# InrushLimiter.net
KiCad netlist of a schematic drawn in Altium Designer
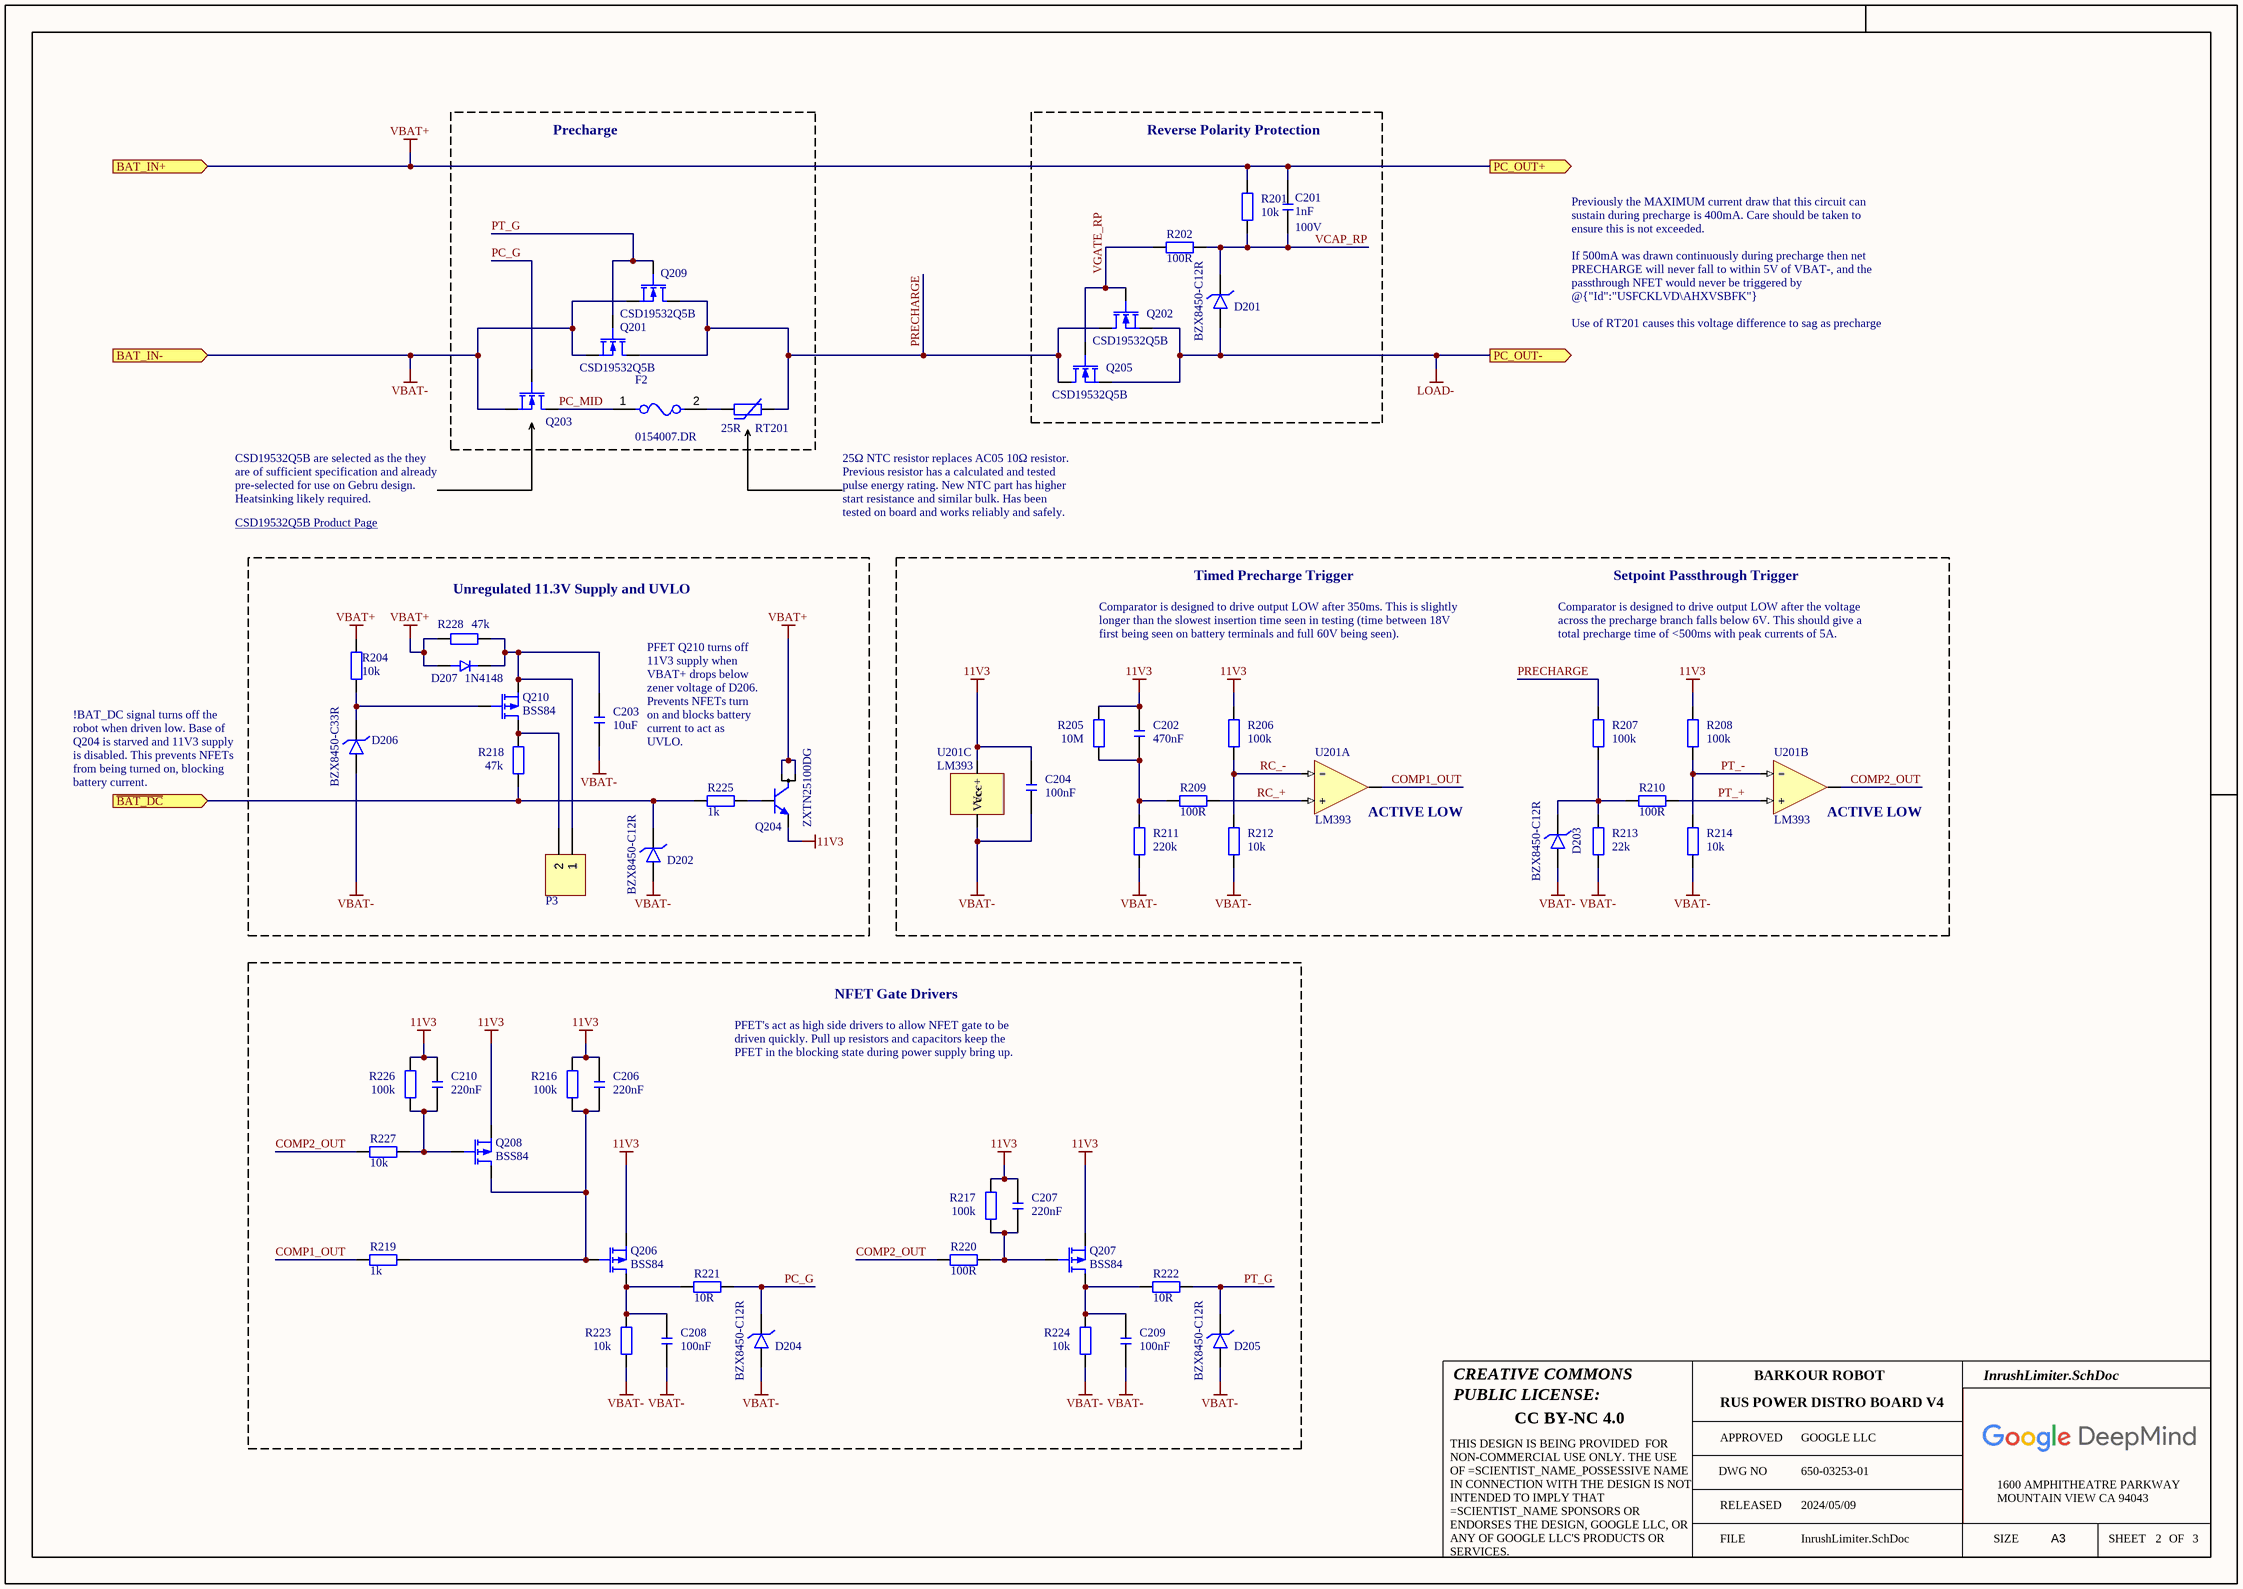
[diagram p0: InrushLimiter.SchDoc]

(export (version "E")
  (design (tool "Eeschema 10.0.6"))
  (components
    (comp (ref "C201")
      (value "1nF")
      (footprint "CAP 0805_2012")
      (description "Generic Capacitor")
      (fields (field (name "TOLERANCE") "20%") (field (name "VOLTAGE RATING") "100V"))
      (libsource (lib "DMR_common_lib") (part "C"))
    )
    (comp (ref "C202")
      (value "470nF")
      (footprint "CAP 0603_1608 RF")
      (description "Generic Capacitor")
      (fields (field (name "TOLERANCE") "10%"))
      (libsource (lib "DMR_common_lib") (part "C"))
    )
    (comp (ref "C203")
      (value "10uF")
      (footprint "CAP 1206_3216")
      (description "Generic Capacitor")
      (fields (field (name "TOLERANCE") "10%"))
      (libsource (lib "DMR_common_lib") (part "C"))
    )
    (comp (ref "C204")
      (value "100nF")
      (footprint "CAP 0603_1608 RF")
      (description "Generic Capacitor")
      (fields (field (name "TOLERANCE") "10%"))
      (libsource (lib "DMR_common_lib") (part "C"))
    )
    (comp (ref "C206")
      (value "220nF")
      (footprint "CAP 0603_1608 RF")
      (description "Generic Capacitor")
      (fields (field (name "TOLERANCE") "10%"))
      (libsource (lib "DMR_common_lib") (part "C"))
    )
    (comp (ref "C207")
      (value "220nF")
      (footprint "CAP 0603_1608 RF")
      (description "Generic Capacitor")
      (fields (field (name "TOLERANCE") "10%"))
      (libsource (lib "DMR_common_lib") (part "C"))
    )
    (comp (ref "C208")
      (value "100nF")
      (footprint "CAP 0603_1608 RF")
      (description "Generic Capacitor")
      (fields (field (name "TOLERANCE") "10%"))
      (libsource (lib "DMR_common_lib") (part "C"))
    )
    (comp (ref "C209")
      (value "100nF")
      (footprint "CAP 0603_1608 RF")
      (description "Generic Capacitor")
      (fields (field (name "TOLERANCE") "10%"))
      (libsource (lib "DMR_common_lib") (part "C"))
    )
    (comp (ref "C210")
      (value "220nF")
      (footprint "CAP 0603_1608 RF")
      (description "Generic Capacitor")
      (fields (field (name "TOLERANCE") "10%"))
      (libsource (lib "DMR_common_lib") (part "C"))
    )
    (comp (ref "D201")
      (value "BZX8450-C12R")
      (footprint "NEXPERIA SOT-23-3")
      (description "Diode Zener Single 12V 5% 250mW 3-Pin SOT-23 T/R")
      (fields (field (name "MANUFACTURER") "Nexperia"))
      (libsource (lib "DMR_common_lib") (part "BZX8450-C12R"))
    )
    (comp (ref "D202")
      (value "BZX8450-C12R")
      (footprint "NEXPERIA SOT-23-3")
      (description "Diode Zener Single 12V 5% 250mW 3-Pin SOT-23 T/R")
      (fields (field (name "MANUFACTURER") "Nexperia"))
      (libsource (lib "DMR_common_lib") (part "BZX8450-C12R"))
    )
    (comp (ref "D203")
      (value "BZX8450-C12R")
      (footprint "NEXPERIA SOT-23-3")
      (description "Diode Zener Single 12V 5% 250mW 3-Pin SOT-23 T/R")
      (fields (field (name "MANUFACTURER") "Nexperia"))
      (libsource (lib "DMR_common_lib") (part "BZX8450-C12R"))
    )
    (comp (ref "D204")
      (value "BZX8450-C12R")
      (footprint "NEXPERIA SOT-23-3")
      (description "Diode Zener Single 12V 5% 250mW 3-Pin SOT-23 T/R")
      (fields (field (name "MANUFACTURER") "Nexperia"))
      (libsource (lib "DMR_common_lib") (part "BZX8450-C12R"))
    )
    (comp (ref "D205")
      (value "BZX8450-C12R")
      (footprint "NEXPERIA SOT-23-3")
      (description "Diode Zener Single 12V 5% 250mW 3-Pin SOT-23 T/R")
      (fields (field (name "MANUFACTURER") "Nexperia"))
      (libsource (lib "DMR_common_lib") (part "BZX8450-C12R"))
    )
    (comp (ref "D206")
      (value "BZX8450-C33R")
      (footprint "NEXPERIA SOT-23-3")
      (description "Zener Diodes BZX8450-C33/SOT23/TO-236AB")
      (fields (field (name "MANUFACTURER") "Nexperia"))
      (libsource (lib "DMR_common_lib") (part "BZX8450-C20R"))
    )
    (comp (ref "D207")
      (value "1N4148WS-7-F")
      (footprint "SOD323")
      (description "Signal Diode VR=75V IF=150mA Trr=4ns P=200mW")
      (fields
        (field (name "MANUFACTURER") "Diodes")
        (field (name "VOLTAGE") "75V")
        (field (name "COLLOQUIAL") "1N4148")
      )
      (libsource (lib "DMR_common_lib") (part "1N4148"))
    )
    (comp (ref "F2")
      (value "0154007.DR")
      (footprint "FP-0154-MFG")
      (description "FUSE BRD MNT 7A 125VAC/VDC 2SMD")
      (fields
        (field (name "OCTOPART") "https://octopart.com/0154007.dr-littelfuse-565863")
        (field (name "MANUFACTURER") "Littelfuse Inc")
      )
      (libsource (lib "Altium Content Vault") (part "5bcf9b9f640e542cf0359d10258e979"))
    )
    (comp (ref "P3")
      (value "Header 2")
      (footprint "HDR1X2")
      (description "Header, 2-Pin")
      (fields (field (name "PUBLISHER") "Altium Limited"))
      (libsource (lib "Miscellaneous Connectors") (part "Header 2"))
    )
    (comp (ref "Q201")
      (value "CSD19532Q5B")
      (footprint "TI SON 5x6")
      (description "100-V, N channel NexFET™ power MOSFET, single SON 5 mm x 6 mm, 4.9 mOhm 8-VSON-CLIP -55 to 150")
      (fields (field (name "MANUFACTURER") "Texas Instruments"))
      (libsource (lib "DMR_common_lib") (part "CSD19532Q5B"))
    )
    (comp (ref "Q202")
      (value "CSD19532Q5B")
      (footprint "TI SON 5x6")
      (description "100-V, N channel NexFET™ power MOSFET, single SON 5 mm x 6 mm, 4.9 mOhm 8-VSON-CLIP -55 to 150")
      (fields (field (name "MANUFACTURER") "Texas Instruments"))
      (libsource (lib "DMR_common_lib") (part "CSD19532Q5B"))
    )
    (comp (ref "Q203")
      (value "CSD19532Q5B")
      (footprint "TI SON 5x6")
      (description "100-V, N channel NexFET™ power MOSFET, single SON 5 mm x 6 mm, 4.9 mOhm 8-VSON-CLIP -55 to 150")
      (fields (field (name "MANUFACTURER") "Texas Instruments"))
      (libsource (lib "DMR_common_lib") (part "CSD19532Q5B"))
    )
    (comp (ref "Q204")
      (value "ZXTN25100DG")
      (footprint "DIODES SOT-223")
      (description "TRANS NPN 100V 3A SOT223")
      (fields (field (name "MANUFACTURER") "Diodes Inc"))
      (libsource (lib "DMR_common_lib") (part "ZXTN25100DG"))
    )
    (comp (ref "Q205")
      (value "CSD19532Q5B")
      (footprint "TI SON 5x6")
      (description "100-V, N channel NexFET™ power MOSFET, single SON 5 mm x 6 mm, 4.9 mOhm 8-VSON-CLIP -55 to 150")
      (fields (field (name "MANUFACTURER") "Texas Instruments"))
      (libsource (lib "DMR_common_lib") (part "CSD19532Q5B"))
    )
    (comp (ref "Q206")
      (value "BSS84W-7-F")
      (footprint "DIODES SOT-323-3")
      (description "P-Channel 50 V 10 Ohm Enhancement Mode Transistor SOT-323")
      (fields (field (name "MANUFACTURER") "Diodes Inc") (field (name "COLLOQUIAL") "BSS84"))
      (libsource (lib "DMR_common_lib") (part "BSS84W"))
    )
    (comp (ref "Q207")
      (value "BSS84W-7-F")
      (footprint "DIODES SOT-323-3")
      (description "P-Channel 50 V 10 Ohm Enhancement Mode Transistor SOT-323")
      (fields (field (name "MANUFACTURER") "Diodes Inc") (field (name "COLLOQUIAL") "BSS84"))
      (libsource (lib "DMR_common_lib") (part "BSS84W"))
    )
    (comp (ref "Q208")
      (value "BSS84W-7-F")
      (footprint "DIODES SOT-323-3")
      (description "P-Channel 50 V 10 Ohm Enhancement Mode Transistor SOT-323")
      (fields (field (name "MANUFACTURER") "Diodes Inc") (field (name "COLLOQUIAL") "BSS84"))
      (libsource (lib "DMR_common_lib") (part "BSS84W"))
    )
    (comp (ref "Q209")
      (value "CSD19532Q5B")
      (footprint "TI SON 5x6")
      (description "100-V, N channel NexFET™ power MOSFET, single SON 5 mm x 6 mm, 4.9 mOhm 8-VSON-CLIP -55 to 150")
      (fields (field (name "MANUFACTURER") "Texas Instruments"))
      (libsource (lib "DMR_common_lib") (part "CSD19532Q5B"))
    )
    (comp (ref "Q210")
      (value "BSS84W-7-F")
      (footprint "DIODES SOT-323-3")
      (description "P-Channel 50 V 10 Ohm Enhancement Mode Transistor SOT-323")
      (fields (field (name "MANUFACTURER") "Diodes Inc") (field (name "COLLOQUIAL") "BSS84"))
      (libsource (lib "DMR_common_lib") (part "BSS84W"))
    )
    (comp (ref "R201")
      (value "10k")
      (footprint "RES 0402_1005 RF")
      (description "Generic Resistor")
      (fields (field (name "TOLERANCE") "1%"))
      (libsource (lib "DMR_common_lib") (part "R"))
    )
    (comp (ref "R202")
      (value "100R")
      (footprint "RES 0402_1005 RF")
      (description "Generic Resistor")
      (fields (field (name "TOLERANCE") "1%"))
      (libsource (lib "") (part "R_2"))
    )
    (comp (ref "R204")
      (value "10k")
      (footprint "RES 0603_1608 RF")
      (description "RES 10K OHM 1% 1/5W 0603")
      (fields (field (name "TOLERANCE") "1%") (field (name "MANUFACTURER") "YAGEO"))
      (libsource (lib "") (part "R_1"))
    )
    (comp (ref "R205")
      (value "10M")
      (footprint "RES 0402_1005 RF")
      (description "Generic Resistor")
      (fields (field (name "TOLERANCE") "1%"))
      (libsource (lib "DMR_common_lib") (part "R"))
    )
    (comp (ref "R206")
      (value "100k")
      (footprint "RES 0402_1005 RF")
      (description "Generic Resistor")
      (fields (field (name "TOLERANCE") "1%"))
      (libsource (lib "DMR_common_lib") (part "R"))
    )
    (comp (ref "R207")
      (value "100k")
      (footprint "RES 0402_1005 RF")
      (description "Generic Resistor")
      (fields (field (name "TOLERANCE") "1%"))
      (libsource (lib "DMR_common_lib") (part "R"))
    )
    (comp (ref "R208")
      (value "100k")
      (footprint "RES 0402_1005 RF")
      (description "Generic Resistor")
      (fields (field (name "TOLERANCE") "1%"))
      (libsource (lib "DMR_common_lib") (part "R"))
    )
    (comp (ref "R209")
      (value "100R")
      (footprint "RES 0402_1005 RF")
      (description "Generic Resistor")
      (fields (field (name "TOLERANCE") "1%"))
      (libsource (lib "") (part "R_2"))
    )
    (comp (ref "R210")
      (value "100R")
      (footprint "RES 0402_1005 RF")
      (description "Generic Resistor")
      (fields (field (name "TOLERANCE") "1%"))
      (libsource (lib "") (part "R_2"))
    )
    (comp (ref "R211")
      (value "220k")
      (footprint "RES 0402_1005 RF")
      (description "Generic Resistor")
      (fields (field (name "TOLERANCE") "1%"))
      (libsource (lib "DMR_common_lib") (part "R"))
    )
    (comp (ref "R212")
      (value "10k")
      (footprint "RES 0402_1005 RF")
      (description "Generic Resistor")
      (fields (field (name "TOLERANCE") "1%"))
      (libsource (lib "DMR_common_lib") (part "R"))
    )
    (comp (ref "R213")
      (value "22k")
      (footprint "RES 0603_1608 RF")
      (description "Generic Resistor")
      (fields (field (name "TOLERANCE") "1%"))
      (libsource (lib "DMR_common_lib") (part "R"))
    )
    (comp (ref "R214")
      (value "10k")
      (footprint "RES 0402_1005 RF")
      (description "Generic Resistor")
      (fields (field (name "TOLERANCE") "1%"))
      (libsource (lib "DMR_common_lib") (part "R"))
    )
    (comp (ref "R216")
      (value "100k")
      (footprint "RES 0402_1005 RF")
      (description "Generic Resistor")
      (fields (field (name "TOLERANCE") "1%"))
      (libsource (lib "") (part "R_1"))
    )
    (comp (ref "R217")
      (value "100k")
      (footprint "RES 0402_1005 RF")
      (description "Generic Resistor")
      (fields (field (name "TOLERANCE") "1%"))
      (libsource (lib "") (part "R_1"))
    )
    (comp (ref "R218")
      (value "47k")
      (footprint "RES 0603_1608 RF")
      (description "Generic Resistor")
      (fields (field (name "TOLERANCE") "1%"))
      (libsource (lib "DMR_common_lib") (part "R"))
    )
    (comp (ref "R219")
      (value "1k")
      (footprint "RES 0402_1005 RF")
      (description "Generic Resistor")
      (fields (field (name "TOLERANCE") "1%"))
      (libsource (lib "") (part "R_2"))
    )
    (comp (ref "R220")
      (value "100R")
      (footprint "RES 0402_1005 RF")
      (description "Generic Resistor")
      (fields (field (name "TOLERANCE") "1%"))
      (libsource (lib "") (part "R_2"))
    )
    (comp (ref "R221")
      (value "10R")
      (footprint "RES 0402_1005 RF")
      (description "Generic Resistor")
      (fields (field (name "TOLERANCE") "1%"))
      (libsource (lib "") (part "R_2"))
    )
    (comp (ref "R222")
      (value "10R")
      (footprint "RES 0402_1005 RF")
      (description "Generic Resistor")
      (fields (field (name "TOLERANCE") "1%"))
      (libsource (lib "") (part "R_2"))
    )
    (comp (ref "R223")
      (value "10k")
      (footprint "RES 0402_1005 RF")
      (description "Generic Resistor")
      (fields (field (name "TOLERANCE") "1%"))
      (libsource (lib "") (part "R_1"))
    )
    (comp (ref "R224")
      (value "10k")
      (footprint "RES 0402_1005 RF")
      (description "Generic Resistor")
      (fields (field (name "TOLERANCE") "1%"))
      (libsource (lib "") (part "R_1"))
    )
    (comp (ref "R225")
      (value "1k")
      (footprint "RES 0603_1608 RF")
      (description "Generic Resistor")
      (fields (field (name "TOLERANCE") "1%"))
      (libsource (lib "") (part "R_2"))
    )
    (comp (ref "R226")
      (value "100k")
      (footprint "RES 0402_1005 RF")
      (description "Generic Resistor")
      (fields (field (name "TOLERANCE") "1%"))
      (libsource (lib "") (part "R_1"))
    )
    (comp (ref "R227")
      (value "10k")
      (footprint "RES 0402_1005 RF")
      (description "Generic Resistor")
      (fields (field (name "TOLERANCE") "1%"))
      (libsource (lib "") (part "R_2"))
    )
    (comp (ref "R228")
      (value "47k")
      (footprint "RES 0603_1608 RF")
      (description "Generic Resistor")
      (fields (field (name "TOLERANCE") "1%"))
      (libsource (lib "") (part "R_2"))
    )
    (comp (ref "RT201")
      (value "25R")
      (footprint "RES THERM TH 16.0 DISC LEADED")
      (description "NTC Thermistor, 25ohm, Through Hole Mount")
      (fields
        (field (name "MANUFACTURER") "Epcos")
        (field (name "MANUFACTURER PART NUMBER") "B57238S0250M000")
      )
      (libsource (lib "DMR_common_lib") (part "B57238S0250M000"))
    )
    (comp (ref "U201")
      (value "LM393PT")
      (footprint "ST TSSOP-8")
      (description "Comparator Dual 18V/36V 8-Pin TSSOP T/R")
      (fields (field (name "MANUFACTURER") "ST") (field (name "COLLOQUIAL") "LM393"))
      (libsource (lib "DMR_common_lib") (part "LM393"))
    )
  )
  (nets
    (net (code "1") (name "/COMP1_OUT") (class "Default")
      (node (ref "R219") (pin "2") (pinfunction "2_2") (pintype "passive"))
      (node (ref "U201") (pin "1") (pinfunction "Out1_1") (pintype "open_collector"))
    )
    (net (code "2") (name "/COMP2_OUT") (class "Default")
      (node (ref "R220") (pin "2") (pinfunction "2_2") (pintype "passive"))
      (node (ref "R227") (pin "2") (pinfunction "2_2") (pintype "passive"))
      (node (ref "U201") (pin "7") (pinfunction "Out1_7") (pintype "open_collector"))
    )
    (net (code "3") (name "/PC_G") (class "Default")
      (node (ref "D204") (pin "3") (pinfunction "K_3") (pintype "passive"))
      (node (ref "Q203") (pin "1") (pinfunction "G_1") (pintype "passive"))
      (node (ref "R221") (pin "1") (pinfunction "1_1") (pintype "passive"))
    )
    (net (code "4") (name "/PC_MID") (class "Default")
      (node (ref "F2") (pin "1") (pinfunction "1_1") (pintype "passive"))
      (node (ref "Q203") (pin "3") (pinfunction "D_3") (pintype "passive"))
    )
    (net (code "5") (name "/PRECHARGE") (class "Default")
      (node (ref "Q201") (pin "3") (pinfunction "D_3") (pintype "passive"))
      (node (ref "Q202") (pin "3") (pinfunction "D_3") (pintype "passive"))
      (node (ref "Q205") (pin "3") (pinfunction "D_3") (pintype "passive"))
      (node (ref "Q209") (pin "3") (pinfunction "D_3") (pintype "passive"))
      (node (ref "R207") (pin "2") (pinfunction "2_2") (pintype "passive"))
      (node (ref "RT201") (pin "2") (pinfunction "2_2") (pintype "passive"))
    )
    (net (code "6") (name "/PT_+") (class "Default")
      (node (ref "R210") (pin "1") (pinfunction "1_1") (pintype "passive"))
      (node (ref "U201") (pin "5") (pinfunction "+_5") (pintype "input"))
    )
    (net (code "7") (name "/PT_-") (class "Default")
      (node (ref "R208") (pin "1") (pinfunction "1_1") (pintype "passive"))
      (node (ref "R214") (pin "2") (pinfunction "2_2") (pintype "passive"))
      (node (ref "U201") (pin "6") (pinfunction "−_6") (pintype "input"))
    )
    (net (code "8") (name "/PT_G") (class "Default")
      (node (ref "D205") (pin "3") (pinfunction "K_3") (pintype "passive"))
      (node (ref "Q201") (pin "1") (pinfunction "G_1") (pintype "passive"))
      (node (ref "Q209") (pin "1") (pinfunction "G_1") (pintype "passive"))
      (node (ref "R222") (pin "1") (pinfunction "1_1") (pintype "passive"))
    )
    (net (code "9") (name "/RC_+") (class "Default")
      (node (ref "R209") (pin "1") (pinfunction "1_1") (pintype "passive"))
      (node (ref "U201") (pin "3") (pinfunction "+_3") (pintype "input"))
    )
    (net (code "10") (name "/RC_-") (class "Default")
      (node (ref "R206") (pin "1") (pinfunction "1_1") (pintype "passive"))
      (node (ref "R212") (pin "2") (pinfunction "2_2") (pintype "passive"))
      (node (ref "U201") (pin "2") (pinfunction "−_2") (pintype "input"))
    )
    (net (code "11") (name "/VCAP_RP") (class "Default")
      (node (ref "C201") (pin "1") (pinfunction "1_1") (pintype "passive"))
      (node (ref "D201") (pin "3") (pinfunction "K_3") (pintype "passive"))
      (node (ref "R201") (pin "1") (pinfunction "1_1") (pintype "passive"))
      (node (ref "R202") (pin "1") (pinfunction "1_1") (pintype "passive"))
    )
    (net (code "12") (name "/VGATE_RP") (class "Default")
      (node (ref "Q202") (pin "1") (pinfunction "G_1") (pintype "passive"))
      (node (ref "Q205") (pin "1") (pinfunction "G_1") (pintype "passive"))
      (node (ref "R202") (pin "2") (pinfunction "2_2") (pintype "passive"))
    )
    (net (code "13") (name "/~{BAT_DC}") (class "Default")
      (node (ref "D202") (pin "3") (pinfunction "K_3") (pintype "passive"))
      (node (ref "R218") (pin "1") (pinfunction "1_1") (pintype "passive"))
      (node (ref "R225") (pin "2") (pinfunction "2_2") (pintype "passive"))
    )
    (net (code "14") (name "11V3") (class "Default")
      (node (ref "C202") (pin "2") (pinfunction "2_2") (pintype "passive"))
      (node (ref "C204") (pin "2") (pinfunction "2_2") (pintype "passive"))
      (node (ref "C206") (pin "2") (pinfunction "2_2") (pintype "passive"))
      (node (ref "C207") (pin "2") (pinfunction "2_2") (pintype "passive"))
      (node (ref "C210") (pin "2") (pinfunction "2_2") (pintype "passive"))
      (node (ref "Q204") (pin "3") (pinfunction "E_3") (pintype "passive"))
      (node (ref "Q206") (pin "3") (pinfunction "S_3") (pintype "passive"))
      (node (ref "Q207") (pin "3") (pinfunction "S_3") (pintype "passive"))
      (node (ref "Q208") (pin "3") (pinfunction "S_3") (pintype "passive"))
      (node (ref "R205") (pin "2") (pinfunction "2_2") (pintype "passive"))
      (node (ref "R206") (pin "2") (pinfunction "2_2") (pintype "passive"))
      (node (ref "R208") (pin "2") (pinfunction "2_2") (pintype "passive"))
      (node (ref "R216") (pin "1") (pinfunction "1_1") (pintype "passive"))
      (node (ref "R217") (pin "1") (pinfunction "1_1") (pintype "passive"))
      (node (ref "R226") (pin "1") (pinfunction "1_1") (pintype "passive"))
      (node (ref "U201") (pin "8") (pinfunction "Vcc+_8") (pintype "power_in"))
    )
    (net (code "15") (name "LOAD-") (class "Default")
      (node (ref "D201") (pin "1") (pinfunction "A_1") (pintype "passive"))
      (node (ref "Q202") (pin "2") (pinfunction "S_2") (pintype "passive"))
      (node (ref "Q205") (pin "2") (pinfunction "S_2") (pintype "passive"))
    )
    (net (code "16") (name "Net-(C202-Pad1)") (class "Default")
      (node (ref "C202") (pin "1") (pinfunction "1_1") (pintype "passive"))
      (node (ref "R205") (pin "1") (pinfunction "1_1") (pintype "passive"))
      (node (ref "R209") (pin "2") (pinfunction "2_2") (pintype "passive"))
      (node (ref "R211") (pin "2") (pinfunction "2_2") (pintype "passive"))
    )
    (net (code "17") (name "Net-(D203-K)") (class "Default")
      (node (ref "D203") (pin "3") (pinfunction "K_3") (pintype "passive"))
      (node (ref "R207") (pin "1") (pinfunction "1_1") (pintype "passive"))
      (node (ref "R210") (pin "2") (pinfunction "2_2") (pintype "passive"))
      (node (ref "R213") (pin "2") (pinfunction "2_2") (pintype "passive"))
    )
    (net (code "18") (name "Net-(D206-K)") (class "Default")
      (node (ref "D206") (pin "3") (pinfunction "K_3") (pintype "passive"))
      (node (ref "Q210") (pin "1") (pinfunction "G_1") (pintype "passive"))
      (node (ref "R204") (pin "2") (pinfunction "2_2") (pintype "passive"))
    )
    (net (code "19") (name "Net-(F2-Pad2)") (class "Default")
      (node (ref "F2") (pin "2") (pinfunction "2_2") (pintype "passive"))
      (node (ref "RT201") (pin "1") (pinfunction "1_1") (pintype "passive"))
    )
    (net (code "20") (name "Net-(Q204-B)") (class "Default")
      (node (ref "Q204") (pin "1") (pinfunction "B_1") (pintype "passive"))
      (node (ref "R225") (pin "1") (pinfunction "1_1") (pintype "passive"))
    )
    (net (code "21") (name "Net-(Q206-D)") (class "Default")
      (node (ref "C208") (pin "2") (pinfunction "2_2") (pintype "passive"))
      (node (ref "Q206") (pin "2") (pinfunction "D_2") (pintype "passive"))
      (node (ref "R221") (pin "2") (pinfunction "2_2") (pintype "passive"))
      (node (ref "R223") (pin "1") (pinfunction "1_1") (pintype "passive"))
    )
    (net (code "22") (name "Net-(Q206-G)") (class "Default")
      (node (ref "C206") (pin "1") (pinfunction "1_1") (pintype "passive"))
      (node (ref "Q206") (pin "1") (pinfunction "G_1") (pintype "passive"))
      (node (ref "Q208") (pin "2") (pinfunction "D_2") (pintype "passive"))
      (node (ref "R216") (pin "2") (pinfunction "2_2") (pintype "passive"))
      (node (ref "R219") (pin "1") (pinfunction "1_1") (pintype "passive"))
    )
    (net (code "23") (name "Net-(Q207-D)") (class "Default")
      (node (ref "C209") (pin "2") (pinfunction "2_2") (pintype "passive"))
      (node (ref "Q207") (pin "2") (pinfunction "D_2") (pintype "passive"))
      (node (ref "R222") (pin "2") (pinfunction "2_2") (pintype "passive"))
      (node (ref "R224") (pin "1") (pinfunction "1_1") (pintype "passive"))
    )
    (net (code "24") (name "Net-(Q207-G)") (class "Default")
      (node (ref "C207") (pin "1") (pinfunction "1_1") (pintype "passive"))
      (node (ref "Q207") (pin "1") (pinfunction "G_1") (pintype "passive"))
      (node (ref "R217") (pin "2") (pinfunction "2_2") (pintype "passive"))
      (node (ref "R220") (pin "1") (pinfunction "1_1") (pintype "passive"))
    )
    (net (code "25") (name "Net-(Q208-G)") (class "Default")
      (node (ref "C210") (pin "1") (pinfunction "1_1") (pintype "passive"))
      (node (ref "Q208") (pin "1") (pinfunction "G_1") (pintype "passive"))
      (node (ref "R226") (pin "2") (pinfunction "2_2") (pintype "passive"))
      (node (ref "R227") (pin "1") (pinfunction "1_1") (pintype "passive"))
    )
    (net (code "26") (name "Net-(Q210-D)") (class "Default")
      (node (ref "P3") (pin "2") (pinfunction "2_2") (pintype "passive"))
      (node (ref "Q210") (pin "2") (pinfunction "D_2") (pintype "passive"))
      (node (ref "R218") (pin "2") (pinfunction "2_2") (pintype "passive"))
    )
    (net (code "27") (name "Net-(Q210-S)") (class "Default")
      (node (ref "C203") (pin "2") (pinfunction "2_2") (pintype "passive"))
      (node (ref "D207") (pin "2") (pinfunction "2_2") (pintype "passive"))
      (node (ref "P3") (pin "1") (pinfunction "1_1") (pintype "passive"))
      (node (ref "Q210") (pin "3") (pinfunction "S_3") (pintype "passive"))
      (node (ref "R228") (pin "1") (pinfunction "1_1") (pintype "passive"))
    )
    (net (code "28") (name "VBAT+") (class "Default")
      (node (ref "C201") (pin "2") (pinfunction "2_2") (pintype "passive"))
      (node (ref "D207") (pin "1") (pinfunction "1_1") (pintype "passive"))
      (node (ref "Q204") (pin "2") (pinfunction "C_2") (pintype "passive"))
      (node (ref "Q204") (pin "4") (pinfunction "C_4") (pintype "passive"))
      (node (ref "R201") (pin "2") (pinfunction "2_2") (pintype "passive"))
      (node (ref "R204") (pin "1") (pinfunction "1_1") (pintype "passive"))
      (node (ref "R228") (pin "2") (pinfunction "2_2") (pintype "passive"))
    )
    (net (code "29") (name "VBAT-") (class "Default")
      (node (ref "C203") (pin "1") (pinfunction "1_1") (pintype "passive"))
      (node (ref "C204") (pin "1") (pinfunction "1_1") (pintype "passive"))
      (node (ref "C208") (pin "1") (pinfunction "1_1") (pintype "passive"))
      (node (ref "C209") (pin "1") (pinfunction "1_1") (pintype "passive"))
      (node (ref "D202") (pin "1") (pinfunction "A_1") (pintype "passive"))
      (node (ref "D203") (pin "1") (pinfunction "A_1") (pintype "passive"))
      (node (ref "D204") (pin "1") (pinfunction "A_1") (pintype "passive"))
      (node (ref "D205") (pin "1") (pinfunction "A_1") (pintype "passive"))
      (node (ref "D206") (pin "1") (pinfunction "A_1") (pintype "passive"))
      (node (ref "Q201") (pin "2") (pinfunction "S_2") (pintype "passive"))
      (node (ref "Q203") (pin "2") (pinfunction "S_2") (pintype "passive"))
      (node (ref "Q209") (pin "2") (pinfunction "S_2") (pintype "passive"))
      (node (ref "R211") (pin "1") (pinfunction "1_1") (pintype "passive"))
      (node (ref "R212") (pin "1") (pinfunction "1_1") (pintype "passive"))
      (node (ref "R213") (pin "1") (pinfunction "1_1") (pintype "passive"))
      (node (ref "R214") (pin "1") (pinfunction "1_1") (pintype "passive"))
      (node (ref "R223") (pin "2") (pinfunction "2_2") (pintype "passive"))
      (node (ref "R224") (pin "2") (pinfunction "2_2") (pintype "passive"))
      (node (ref "U201") (pin "4") (pinfunction "Vcc-_4") (pintype "power_in"))
    )
  )
)
